# 1_Sheet_1.net
KiCad netlist of a schematic drawn in Altium Designer
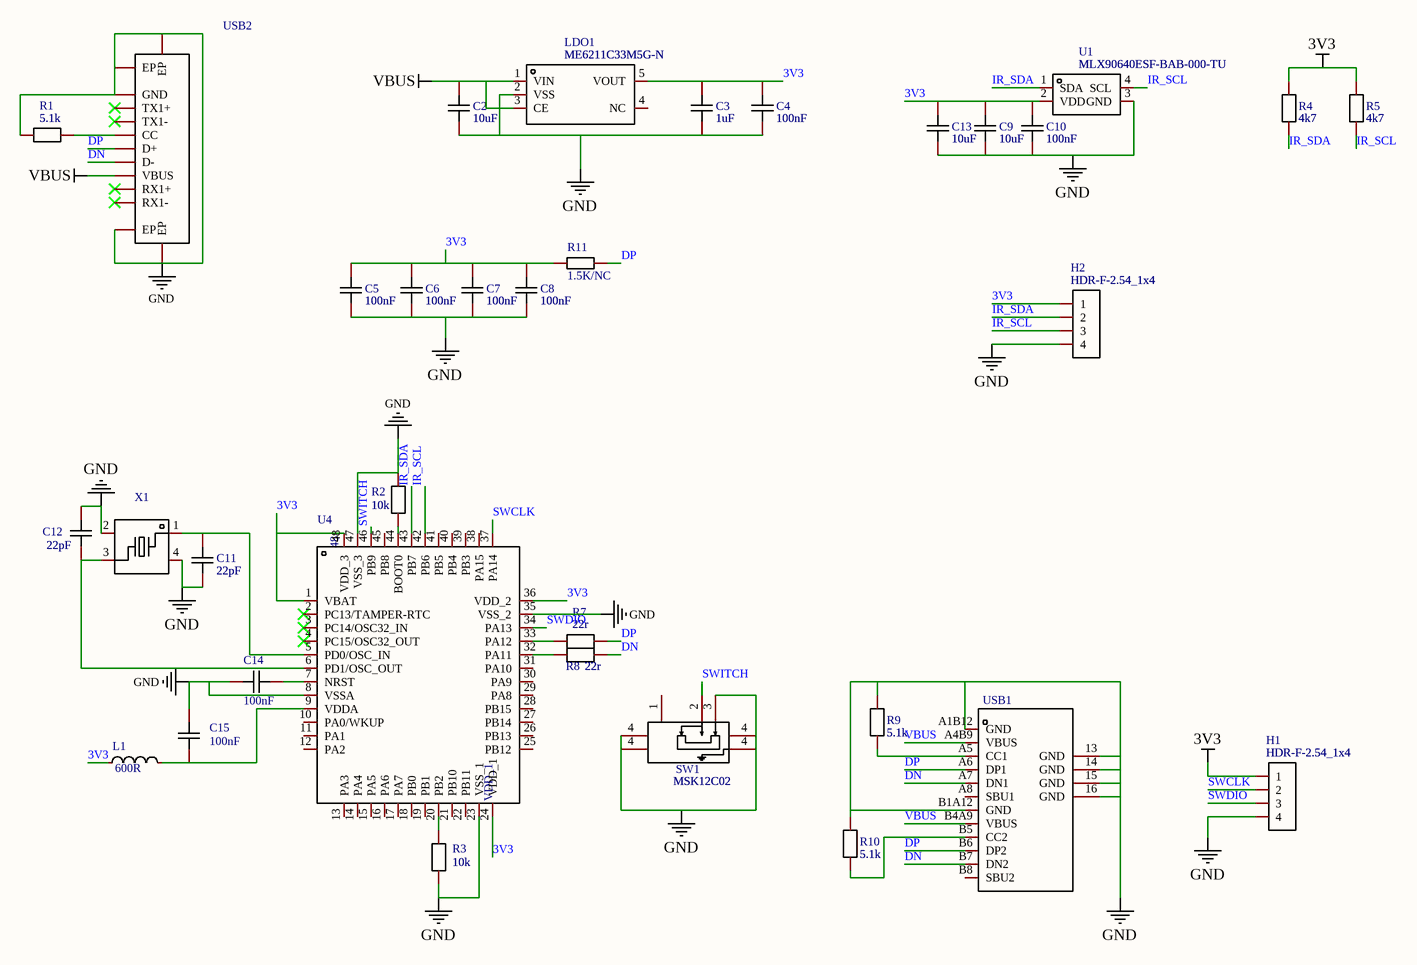
[diagram p0: 1_Sheet_1.schdoc]

(export (version "E")
  (design (tool "Eeschema 10.0.6"))
  (components
    (comp (ref "C2")
      (value "10uF")
      (fields (field (name "NAME") "10uF"))
      (libsource (lib "altium-import") (part "root_1_1uF_"))
    )
    (comp (ref "C3")
      (value "1uF")
      (fields (field (name "NAME") "1uF"))
      (libsource (lib "altium-import") (part "root_1_1uF_"))
    )
    (comp (ref "C4")
      (value "100nF")
      (fields (field (name "NAME") "100nF"))
      (libsource (lib "altium-import") (part "root_1_100nF_"))
    )
    (comp (ref "C5")
      (value "100nF")
      (fields (field (name "NAME") "100nF"))
      (libsource (lib "altium-import") (part "root_1_100nF_"))
    )
    (comp (ref "C6")
      (value "100nF")
      (fields (field (name "NAME") "100nF"))
      (libsource (lib "altium-import") (part "root_1_100nF_"))
    )
    (comp (ref "C7")
      (value "100nF")
      (fields (field (name "NAME") "100nF"))
      (libsource (lib "altium-import") (part "root_1_100nF_"))
    )
    (comp (ref "C8")
      (value "100nF")
      (fields (field (name "NAME") "100nF"))
      (libsource (lib "altium-import") (part "root_1_100nF_"))
    )
    (comp (ref "C9")
      (value "10uF")
      (fields (field (name "NAME") "10uF"))
      (libsource (lib "altium-import") (part "root_1_10uF_"))
    )
    (comp (ref "C10")
      (value "100nF")
      (fields (field (name "NAME") "100nF"))
      (libsource (lib "altium-import") (part "root_1_100nF_"))
    )
    (comp (ref "C11")
      (value "22pF")
      (fields (field (name "NAME") "22pF"))
      (libsource (lib "altium-import") (part "root_1_22pF_"))
    )
    (comp (ref "C12")
      (value "22pF")
      (fields (field (name "NAME") "22pF"))
      (libsource (lib "altium-import") (part "root_1_22pF_"))
    )
    (comp (ref "C13")
      (value "10uF")
      (fields (field (name "NAME") "10uF"))
      (libsource (lib "altium-import") (part "root_1_10uF_"))
    )
    (comp (ref "C14")
      (value "100nF")
      (fields (field (name "Comment") "CAP_0603"))
      (libsource (lib "altium-import") (part "root_0_CAP_0603_"))
    )
    (comp (ref "C15")
      (value "100nF")
      (fields (field (name "Comment") "CAP_0603"))
      (libsource (lib "altium-import") (part "root_3_CAP_0603_"))
    )
    (comp (ref "H1")
      (value "HDR-F-2.54_1x4")
      (fields (field (name "NAME") "HDR-F-2.54_1x4"))
      (libsource (lib "altium-import") (part "root_0_HDR-F-2.54_1x4_"))
    )
    (comp (ref "H2")
      (value "HDR-F-2.54_1x4")
      (fields (field (name "NAME") "HDR-F-2.54_1x4"))
      (libsource (lib "altium-import") (part "root_0_HDR-F-2.54_1x4_"))
    )
    (comp (ref "L1")
      (value "600R")
      (fields (field (name "Comment") "L_0603"))
      (libsource (lib "altium-import") (part "root_0_L_0603_"))
    )
    (comp (ref "LDO1")
      (value "ME6211C33M5G-N")
      (fields (field (name "NAME") "ME6211C33M5G-N") (field (name "MANUFACTURER") "MICRONE"))
      (libsource (lib "altium-import") (part "root_0_ME6211C33M5G-N_"))
    )
    (comp (ref "R1")
      (value "5.1k")
      (fields (field (name "NAME") "5.1k"))
      (libsource (lib "altium-import") (part "root_0_5.1k_"))
    )
    (comp (ref "R2")
      (value "10k")
      (fields (field (name "NAME") "10k"))
      (libsource (lib "altium-import") (part "root_1_1k_"))
    )
    (comp (ref "R3")
      (value "10k")
      (fields (field (name "NAME") "10k"))
      (libsource (lib "altium-import") (part "root_1_1k_"))
    )
    (comp (ref "R4")
      (value "4k7")
      (fields (field (name "NAME") "4k7"))
      (libsource (lib "altium-import") (part "root_1_4k7_"))
    )
    (comp (ref "R5")
      (value "4k7")
      (fields (field (name "NAME") "4k7"))
      (libsource (lib "altium-import") (part "root_1_4k7_"))
    )
    (comp (ref "R7")
      (value "22r")
      (fields (field (name "NAME") "22r"))
      (libsource (lib "altium-import") (part "root_0_22r_"))
    )
    (comp (ref "R8")
      (value "22r")
      (fields (field (name "NAME") "22r"))
      (libsource (lib "altium-import") (part "root_0_22r_"))
    )
    (comp (ref "R9")
      (value "5.1k")
      (fields (field (name "NAME") "5.1k"))
      (libsource (lib "altium-import") (part "root_3_5.1k_"))
    )
    (comp (ref "R10")
      (value "5.1k")
      (fields (field (name "NAME") "5.1k"))
      (libsource (lib "altium-import") (part "root_3_5.1k_"))
    )
    (comp (ref "R11")
      (value "1.5K/NC")
      (fields (field (name "Comment") "Res_0603"))
      (libsource (lib "altium-import") (part "root_0_Res_0603_"))
    )
    (comp (ref "SW1")
      (value "MSK12C02")
      (fields (field (name "NAME") "MSK12C02") (field (name "MANUFACTURER") "SHOU HAN"))
      (libsource (lib "altium-import") (part "root_0_MSK12C02_"))
    )
    (comp (ref "U1")
      (value "MLX90640ESF-BAB-000-TU")
      (fields (field (name "NAME") "MLX90640ESF-BAB-000-TU") (field (name "MANUFACTURER") "Melexis(比利时迈来芯)"))
      (libsource (lib "altium-import") (part "root_0_MLX90640ESF-BAB-000-TU_"))
    )
    (comp (ref "U4")
      (value "AT32F403ACGT7")
      (fields
        (field (name "MANUFACTURER") "ARTERY（雅特力）")
        (field (name "NAME") "VDD_1")
        (field (name "NUMBER") "48")
      )
      (libsource (lib "altium-import") (part "root_0_AT32F403ACGT7_"))
    )
    (comp (ref "USB1")
      (value "TYPEC-304-BCP16")
      (fields (field (name "MANUFACTURER") "XUNPU"))
      (libsource (lib "altium-import") (part "root_0_TYPEC-304-BCP16_"))
    )
    (comp (ref "USB2")
      (value "TYPEC公头9P贴片沉板")
      (libsource (lib "altium-import") (part "root_0_TYPEC公头9P贴片沉板_"))
    )
    (comp (ref "X1")
      (value "CJ13-120001210B20")
      (fields (field (name "MANUFACTURER") "CJ（江苏长电/长晶）"))
      (libsource (lib "altium-import") (part "root_2_CJ13-120001210B20_"))
    )
  )
  (nets
    (net (code "1") (name "/DN") (class "Default")
      (node (ref "R8") (pin "2") (pinfunction "2_2") (pintype "passive"))
      (node (ref "USB1") (pin "A7") (pinfunction "DN1_A7") (pintype "passive"))
      (node (ref "USB1") (pin "B7") (pinfunction "DN2_B7") (pintype "passive"))
      (node (ref "USB2") (pin "A7") (pinfunction "D-_A7") (pintype "passive"))
    )
    (net (code "2") (name "/DP") (class "Default")
      (node (ref "R11") (pin "2") (pinfunction "2_2") (pintype "passive"))
      (node (ref "R7") (pin "2") (pinfunction "2_2") (pintype "passive"))
      (node (ref "USB1") (pin "A6") (pinfunction "DP1_A6") (pintype "passive"))
      (node (ref "USB1") (pin "B6") (pinfunction "DP2_B6") (pintype "passive"))
      (node (ref "USB2") (pin "A6") (pinfunction "D+_A6") (pintype "passive"))
    )
    (net (code "3") (name "/IR_SCL") (class "Default")
      (node (ref "H2") (pin "3") (pinfunction "3_3") (pintype "passive"))
      (node (ref "R5") (pin "1") (pinfunction "1_1") (pintype "passive"))
      (node (ref "U1") (pin "4") (pinfunction "SCL_4") (pintype "passive"))
      (node (ref "U4") (pin "42") (pinfunction "PB6_42") (pintype "passive"))
    )
    (net (code "4") (name "/IR_SDA") (class "Default")
      (node (ref "H2") (pin "2") (pinfunction "2_2") (pintype "passive"))
      (node (ref "R4") (pin "1") (pinfunction "1_1") (pintype "passive"))
      (node (ref "U1") (pin "1") (pinfunction "SDA_1") (pintype "passive"))
      (node (ref "U4") (pin "43") (pinfunction "PB7_43") (pintype "passive"))
    )
    (net (code "5") (name "/SWCLK") (class "Default")
      (node (ref "H1") (pin "2") (pinfunction "2_2") (pintype "passive"))
      (node (ref "U4") (pin "37") (pinfunction "PA14_37") (pintype "passive"))
    )
    (net (code "6") (name "/SWDIO") (class "Default")
      (node (ref "H1") (pin "3") (pinfunction "3_3") (pintype "passive"))
      (node (ref "U4") (pin "34") (pinfunction "PA13_34") (pintype "passive"))
    )
    (net (code "7") (name "/SWITCH") (class "Default")
      (node (ref "SW1") (pin "2") (pinfunction "2_2") (pintype "passive"))
      (node (ref "U4") (pin "46") (pinfunction "PB9_46") (pintype "passive"))
    )
    (net (code "8") (name "3V3") (class "Default")
      (node (ref "C10") (pin "2") (pinfunction "2_2") (pintype "passive"))
      (node (ref "C13") (pin "2") (pinfunction "2_2") (pintype "passive"))
      (node (ref "C3") (pin "2") (pinfunction "2_2") (pintype "passive"))
      (node (ref "C4") (pin "2") (pinfunction "2_2") (pintype "passive"))
      (node (ref "C5") (pin "2") (pinfunction "2_2") (pintype "passive"))
      (node (ref "C6") (pin "2") (pinfunction "2_2") (pintype "passive"))
      (node (ref "C7") (pin "2") (pinfunction "2_2") (pintype "passive"))
      (node (ref "C8") (pin "2") (pinfunction "2_2") (pintype "passive"))
      (node (ref "C9") (pin "2") (pinfunction "2_2") (pintype "passive"))
      (node (ref "H1") (pin "1") (pinfunction "1_1") (pintype "passive"))
      (node (ref "H2") (pin "1") (pinfunction "1_1") (pintype "passive"))
      (node (ref "L1") (pin "1") (pinfunction "1_1") (pintype "passive"))
      (node (ref "LDO1") (pin "5") (pinfunction "VOUT_5") (pintype "passive"))
      (node (ref "R11") (pin "1") (pinfunction "1_1") (pintype "passive"))
      (node (ref "R4") (pin "2") (pinfunction "2_2") (pintype "passive"))
      (node (ref "R5") (pin "2") (pinfunction "2_2") (pintype "passive"))
      (node (ref "U1") (pin "2") (pinfunction "VDD_2") (pintype "passive"))
      (node (ref "U4") (pin "1") (pinfunction "VBAT_1") (pintype "passive"))
      (node (ref "U4") (pin "24") (pinfunction "VDD_1_24") (pintype "passive"))
      (node (ref "U4") (pin "36") (pinfunction "VDD_2_36") (pintype "passive"))
      (node (ref "U4") (pin "48") (pinfunction "VDD_3_48") (pintype "passive"))
    )
    (net (code "9") (name "GND") (class "Default")
      (node (ref "C10") (pin "1") (pinfunction "1_1") (pintype "passive"))
      (node (ref "C11") (pin "1") (pinfunction "1_1") (pintype "passive"))
      (node (ref "C12") (pin "2") (pinfunction "2_2") (pintype "passive"))
      (node (ref "C13") (pin "1") (pinfunction "1_1") (pintype "passive"))
      (node (ref "C14") (pin "1") (pinfunction "1_1") (pintype "passive"))
      (node (ref "C15") (pin "1") (pinfunction "1_1") (pintype "passive"))
      (node (ref "C2") (pin "1") (pinfunction "1_1") (pintype "passive"))
      (node (ref "C3") (pin "1") (pinfunction "1_1") (pintype "passive"))
      (node (ref "C4") (pin "1") (pinfunction "1_1") (pintype "passive"))
      (node (ref "C5") (pin "1") (pinfunction "1_1") (pintype "passive"))
      (node (ref "C6") (pin "1") (pinfunction "1_1") (pintype "passive"))
      (node (ref "C7") (pin "1") (pinfunction "1_1") (pintype "passive"))
      (node (ref "C8") (pin "1") (pinfunction "1_1") (pintype "passive"))
      (node (ref "C9") (pin "1") (pinfunction "1_1") (pintype "passive"))
      (node (ref "H1") (pin "4") (pinfunction "4_4") (pintype "passive"))
      (node (ref "H2") (pin "4") (pinfunction "4_4") (pintype "passive"))
      (node (ref "LDO1") (pin "2") (pinfunction "VSS_2") (pintype "passive"))
      (node (ref "R1") (pin "1") (pinfunction "1_1") (pintype "passive"))
      (node (ref "R10") (pin "1") (pinfunction "1_1") (pintype "passive"))
      (node (ref "R2") (pin "2") (pinfunction "2_2") (pintype "passive"))
      (node (ref "R3") (pin "1") (pinfunction "1_1") (pintype "passive"))
      (node (ref "R9") (pin "1") (pinfunction "1_1") (pintype "passive"))
      (node (ref "SW1") (pin "3") (pinfunction "3_3") (pintype "passive"))
      (node (ref "SW1") (pin "4") (pinfunction "4_4") (pintype "passive"))
      (node (ref "U1") (pin "3") (pinfunction "GND_3") (pintype "passive"))
      (node (ref "U4") (pin "23") (pinfunction "VSS_1_23") (pintype "passive"))
      (node (ref "U4") (pin "35") (pinfunction "VSS_2_35") (pintype "passive"))
      (node (ref "U4") (pin "47") (pinfunction "VSS_3_47") (pintype "passive"))
      (node (ref "U4") (pin "8") (pinfunction "VSSA_8") (pintype "passive"))
      (node (ref "USB1") (pin "13") (pinfunction "GND_13") (pintype "passive"))
      (node (ref "USB1") (pin "14") (pinfunction "GND_14") (pintype "passive"))
      (node (ref "USB1") (pin "15") (pinfunction "GND_15") (pintype "passive"))
      (node (ref "USB1") (pin "16") (pinfunction "GND_16") (pintype "passive"))
      (node (ref "USB1") (pin "A1B12") (pinfunction "GND_A1B12") (pintype "passive"))
      (node (ref "USB1") (pin "B1A12") (pinfunction "GND_B1A12") (pintype "passive"))
      (node (ref "USB2") (pin "A1") (pinfunction "GND_A1") (pintype "passive"))
      (node (ref "USB2") (pin "GND1") (pinfunction "EP_GND1") (pintype "passive"))
      (node (ref "USB2") (pin "GND2") (pinfunction "EP_GND2") (pintype "passive"))
      (node (ref "USB2") (pin "GND3") (pinfunction "EP_GND3") (pintype "passive"))
      (node (ref "USB2") (pin "GND4") (pinfunction "EP_GND4") (pintype "passive"))
      (node (ref "X1") (pin "2") (pinfunction "GND_2") (pintype "passive"))
      (node (ref "X1") (pin "4") (pinfunction "GND_4") (pintype "passive"))
    )
    (net (code "10") (name "Net-(U4-BOOT0)") (class "Default")
      (node (ref "R2") (pin "1") (pinfunction "1_1") (pintype "passive"))
      (node (ref "U4") (pin "44") (pinfunction "BOOT0_44") (pintype "passive"))
    )
    (net (code "11") (name "Net-(U4-NRST)") (class "Default")
      (node (ref "C14") (pin "2") (pinfunction "2_2") (pintype "passive"))
      (node (ref "U4") (pin "7") (pinfunction "NRST_7") (pintype "passive"))
    )
    (net (code "12") (name "Net-(U4-PA11)") (class "Default")
      (node (ref "R8") (pin "1") (pinfunction "1_1") (pintype "passive"))
      (node (ref "U4") (pin "32") (pinfunction "PA11_32") (pintype "passive"))
    )
    (net (code "13") (name "Net-(U4-PA12)") (class "Default")
      (node (ref "R7") (pin "1") (pinfunction "1_1") (pintype "passive"))
      (node (ref "U4") (pin "33") (pinfunction "PA12_33") (pintype "passive"))
    )
    (net (code "14") (name "Net-(U4-PB2)") (class "Default")
      (node (ref "R3") (pin "2") (pinfunction "2_2") (pintype "passive"))
      (node (ref "U4") (pin "20") (pinfunction "PB2_20") (pintype "passive"))
    )
    (net (code "15") (name "Net-(U4-PD0{slash}OSC_IN)") (class "Default")
      (node (ref "C11") (pin "2") (pinfunction "2_2") (pintype "passive"))
      (node (ref "U4") (pin "5") (pinfunction "PD0/OSC_IN_5") (pintype "passive"))
      (node (ref "X1") (pin "1") (pinfunction "1_1") (pintype "passive"))
    )
    (net (code "16") (name "Net-(U4-PD1{slash}OSC_OUT)") (class "Default")
      (node (ref "C12") (pin "1") (pinfunction "1_1") (pintype "passive"))
      (node (ref "U4") (pin "6") (pinfunction "PD1/OSC_OUT_6") (pintype "passive"))
      (node (ref "X1") (pin "3") (pinfunction "3_3") (pintype "passive"))
    )
    (net (code "17") (name "Net-(U4-VDDA)") (class "Default")
      (node (ref "C15") (pin "2") (pinfunction "2_2") (pintype "passive"))
      (node (ref "L1") (pin "2") (pinfunction "2_2") (pintype "passive"))
      (node (ref "U4") (pin "9") (pinfunction "VDDA_9") (pintype "passive"))
    )
    (net (code "18") (name "Net-(USB1-CC1)") (class "Default")
      (node (ref "R9") (pin "2") (pinfunction "2_2") (pintype "passive"))
      (node (ref "USB1") (pin "A5") (pinfunction "CC1_A5") (pintype "passive"))
    )
    (net (code "19") (name "Net-(USB1-CC2)") (class "Default")
      (node (ref "R10") (pin "2") (pinfunction "2_2") (pintype "passive"))
      (node (ref "USB1") (pin "B5") (pinfunction "CC2_B5") (pintype "passive"))
    )
    (net (code "20") (name "Net-(USB2-CC)") (class "Default")
      (node (ref "R1") (pin "2") (pinfunction "2_2") (pintype "passive"))
      (node (ref "USB2") (pin "A5") (pinfunction "CC_A5") (pintype "passive"))
    )
    (net (code "21") (name "VBUS") (class "Default")
      (node (ref "C2") (pin "2") (pinfunction "2_2") (pintype "passive"))
      (node (ref "LDO1") (pin "1") (pinfunction "VIN_1") (pintype "passive"))
      (node (ref "LDO1") (pin "3") (pinfunction "CE_3") (pintype "passive"))
      (node (ref "USB1") (pin "A4B9") (pinfunction "VBUS_A4B9") (pintype "passive"))
      (node (ref "USB1") (pin "B4A9") (pinfunction "VBUS_B4A9") (pintype "passive"))
      (node (ref "USB2") (pin "A9") (pinfunction "VBUS_A9") (pintype "passive"))
    )
    (net (code "22") (name "unconnected-(LDO1-NC-Pad4)") (class "Default")
      (node (ref "LDO1") (pin "4") (pinfunction "NC_4") (pintype "passive"))
    )
    (net (code "23") (name "unconnected-(SW1-Pad1)") (class "Default")
      (node (ref "SW1") (pin "1") (pinfunction "1_1") (pintype "passive"))
    )
    (net (code "24") (name "unconnected-(U4-PA0{slash}WKUP-Pad10)") (class "Default")
      (node (ref "U4") (pin "10") (pinfunction "PA0/WKUP_10") (pintype "passive"))
    )
    (net (code "25") (name "unconnected-(U4-PA1-Pad11)") (class "Default")
      (node (ref "U4") (pin "11") (pinfunction "PA1_11") (pintype "passive"))
    )
    (net (code "26") (name "unconnected-(U4-PA2-Pad12)") (class "Default")
      (node (ref "U4") (pin "12") (pinfunction "PA2_12") (pintype "passive"))
    )
    (net (code "27") (name "unconnected-(U4-PA3-Pad13)") (class "Default")
      (node (ref "U4") (pin "13") (pinfunction "PA3_13") (pintype "passive"))
    )
    (net (code "28") (name "unconnected-(U4-PA4-Pad14)") (class "Default")
      (node (ref "U4") (pin "14") (pinfunction "PA4_14") (pintype "passive"))
    )
    (net (code "29") (name "unconnected-(U4-PA5-Pad15)") (class "Default")
      (node (ref "U4") (pin "15") (pinfunction "PA5_15") (pintype "passive"))
    )
    (net (code "30") (name "unconnected-(U4-PA6-Pad16)") (class "Default")
      (node (ref "U4") (pin "16") (pinfunction "PA6_16") (pintype "passive"))
    )
    (net (code "31") (name "unconnected-(U4-PA7-Pad17)") (class "Default")
      (node (ref "U4") (pin "17") (pinfunction "PA7_17") (pintype "passive"))
    )
    (net (code "32") (name "unconnected-(U4-PA8-Pad29)") (class "Default")
      (node (ref "U4") (pin "29") (pinfunction "PA8_29") (pintype "passive"))
    )
    (net (code "33") (name "unconnected-(U4-PA9-Pad30)") (class "Default")
      (node (ref "U4") (pin "30") (pinfunction "PA9_30") (pintype "passive"))
    )
    (net (code "34") (name "unconnected-(U4-PA10-Pad31)") (class "Default")
      (node (ref "U4") (pin "31") (pinfunction "PA10_31") (pintype "passive"))
    )
    (net (code "35") (name "unconnected-(U4-PA15-Pad38)") (class "Default")
      (node (ref "U4") (pin "38") (pinfunction "PA15_38") (pintype "passive"))
    )
    (net (code "36") (name "unconnected-(U4-PB0-Pad18)") (class "Default")
      (node (ref "U4") (pin "18") (pinfunction "PB0_18") (pintype "passive"))
    )
    (net (code "37") (name "unconnected-(U4-PB1-Pad19)") (class "Default")
      (node (ref "U4") (pin "19") (pinfunction "PB1_19") (pintype "passive"))
    )
    (net (code "38") (name "unconnected-(U4-PB3-Pad39)") (class "Default")
      (node (ref "U4") (pin "39") (pinfunction "PB3_39") (pintype "passive"))
    )
    (net (code "39") (name "unconnected-(U4-PB4-Pad40)") (class "Default")
      (node (ref "U4") (pin "40") (pinfunction "PB4_40") (pintype "passive"))
    )
    (net (code "40") (name "unconnected-(U4-PB5-Pad41)") (class "Default")
      (node (ref "U4") (pin "41") (pinfunction "PB5_41") (pintype "passive"))
    )
    (net (code "41") (name "unconnected-(U4-PB8-Pad45)") (class "Default")
      (node (ref "U4") (pin "45") (pinfunction "PB8_45") (pintype "passive"))
    )
    (net (code "42") (name "unconnected-(U4-PB10-Pad21)") (class "Default")
      (node (ref "U4") (pin "21") (pinfunction "PB10_21") (pintype "passive"))
    )
    (net (code "43") (name "unconnected-(U4-PB11-Pad22)") (class "Default")
      (node (ref "U4") (pin "22") (pinfunction "PB11_22") (pintype "passive"))
    )
    (net (code "44") (name "unconnected-(U4-PB12-Pad25)") (class "Default")
      (node (ref "U4") (pin "25") (pinfunction "PB12_25") (pintype "passive"))
    )
    (net (code "45") (name "unconnected-(U4-PB13-Pad26)") (class "Default")
      (node (ref "U4") (pin "26") (pinfunction "PB13_26") (pintype "passive"))
    )
    (net (code "46") (name "unconnected-(U4-PB14-Pad27)") (class "Default")
      (node (ref "U4") (pin "27") (pinfunction "PB14_27") (pintype "passive"))
    )
    (net (code "47") (name "unconnected-(U4-PB15-Pad28)") (class "Default")
      (node (ref "U4") (pin "28") (pinfunction "PB15_28") (pintype "passive"))
    )
    (net (code "48") (name "unconnected-(U4-PC13{slash}TAMPER-RTC-Pad2)") (class "Default")
      (node (ref "U4") (pin "2") (pinfunction "PC13/TAMPER-RTC_2") (pintype "passive+no_connect"))
    )
    (net (code "49") (name "unconnected-(U4-PC14{slash}OSC32_IN-Pad3)") (class "Default")
      (node (ref "U4") (pin "3") (pinfunction "PC14/OSC32_IN_3") (pintype "passive+no_connect"))
    )
    (net (code "50") (name "unconnected-(U4-PC15{slash}OSC32_OUT-Pad4)") (class "Default")
      (node (ref "U4") (pin "4") (pinfunction "PC15/OSC32_OUT_4") (pintype "passive+no_connect"))
    )
    (net (code "51") (name "unconnected-(USB1-SBU1-PadA8)") (class "Default")
      (node (ref "USB1") (pin "A8") (pinfunction "SBU1_A8") (pintype "passive"))
    )
    (net (code "52") (name "unconnected-(USB1-SBU2-PadB8)") (class "Default")
      (node (ref "USB1") (pin "B8") (pinfunction "SBU2_B8") (pintype "passive"))
    )
    (net (code "53") (name "unconnected-(USB2-RX1+-PadB11)") (class "Default")
      (node (ref "USB2") (pin "B11") (pinfunction "RX1+_B11") (pintype "passive+no_connect"))
    )
    (net (code "54") (name "unconnected-(USB2-RX1--PadB10)") (class "Default")
      (node (ref "USB2") (pin "B10") (pinfunction "RX1-_B10") (pintype "passive+no_connect"))
    )
    (net (code "55") (name "unconnected-(USB2-TX1+-PadA2)") (class "Default")
      (node (ref "USB2") (pin "A2") (pinfunction "TX1+_A2") (pintype "passive+no_connect"))
    )
    (net (code "56") (name "unconnected-(USB2-TX1--PadA3)") (class "Default")
      (node (ref "USB2") (pin "A3") (pinfunction "TX1-_A3") (pintype "passive+no_connect"))
    )
  )
)
